# HotelRail.net
KiCad netlist of a schematic drawn in Altium Designer
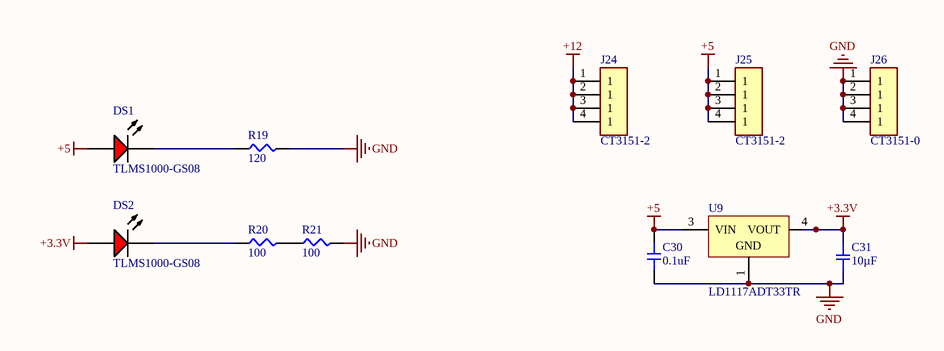
[diagram p0: HotelRail.SchDoc]

(export (version "E")
  (design (tool "Eeschema 10.0.6"))
  (components
    (comp (ref "C30")
      (value "0.1uF")
      (description "0.1uF, 0603, +/- 10%, 50V, X7R")
      (fields (field (name "TOLERANCE") "+/- 10%") (field (name "MFG") "TDK Corporation"))
      (libsource (lib "PV Buck v2 Lib") (part "C1608X7R1H104K080AA"))
    )
    (comp (ref "C31")
      (value "10µF")
      (footprint "PV Buck v2 Lib:SMD-0603-RES")
      (description "CAP CER 10UF 6.3V X5R 0603")
      (fields
        (field (name "PART NUMBER") "GRM188R60J106ME47D")
        (field (name "DIGI-KEY PART NUMBER") "490-3896-1-ND")
      )
      (libsource (lib "PV Buck v2 Lib") (part "GRM188R60J106ME47D"))
    )
    (comp (ref "DS1")
      (value "TLMS1000-GS08")
      (footprint "VISH-TLMS1000_V")
      (description "Low Current LED, 40 mW, 1.8 V, -40 to 100 degC, 2-Pin SMD (0603), RoHS, Tape and Reel")
      (fields (field (name "MANUFACTURER") "Vishay"))
      (libsource (lib "PV Buck v2 Lib") (part "CMP-2000-07254-1"))
    )
    (comp (ref "DS2")
      (value "TLMS1000-GS08")
      (footprint "VISH-TLMS1000_V")
      (description "Low Current LED, 40 mW, 1.8 V, -40 to 100 degC, 2-Pin SMD (0603), RoHS, Tape and Reel")
      (fields (field (name "MANUFACTURER") "Vishay"))
      (libsource (lib "PV Buck v2 Lib") (part "CMP-2000-07254-1"))
    )
    (comp (ref "J24")
      (value "CT3151-2")
      (footprint "CALTEST_CT3151-2")
      (description "Banana Jack Connector Standard Banana Solder Red")
      (fields (field (name "MF") "{'manufacturer': u'Cal Test'}"))
      (libsource (lib "PV Buck v2 Lib") (part "CT3151-2_1"))
    )
    (comp (ref "J25")
      (value "CT3151-2")
      (footprint "CALTEST_CT3151-2")
      (description "Banana Jack Connector Standard Banana Solder Red")
      (fields (field (name "MF") "{'manufacturer': u'Cal Test'}"))
      (libsource (lib "PV Buck v2 Lib") (part "CT3151-2_1"))
    )
    (comp (ref "J26")
      (value "CT3151-0")
      (footprint "CT3151-0")
      (description "Banana Jack Connector Standard Banana Solder Red")
      (fields (field (name "MF") "{'manufacturer': u'Cal Test'}") (field (name "MP") "CT3151-2"))
      (libsource (lib "PV Buck v2 Lib") (part "CT3151-2"))
    )
    (comp (ref "R19")
      (value "120")
      (footprint "SMD-0603-RES")
      (description "RES SMD 120 OHM 1% 1/10W 0603")
      (fields (field (name "PART NUMBER") "ERJ-3EKF1200V") (field (name "DIGI-KEY PART NUMBER") "P120HCT-ND"))
      (libsource (lib "PV Buck v2 Lib") (part "ERJ-3EKF1200V"))
    )
    (comp (ref "R20")
      (value "100")
      (footprint "SMD-0603-RES")
      (description "RES SMD 100 OHM 1% 1/10W 0603")
      (fields (field (name "PART NUMBER") "ERJ-3EKF1000V") (field (name "DIGI-KEY PART NUMBER") "P100HCT-ND"))
      (libsource (lib "PV Buck v2 Lib") (part "ERJ-3EKF1000V"))
    )
    (comp (ref "R21")
      (value "100")
      (footprint "SMD-0603-RES")
      (description "RES SMD 100 OHM 1% 1/10W 0603")
      (fields (field (name "PART NUMBER") "ERJ-3EKF1000V") (field (name "DIGI-KEY PART NUMBER") "P100HCT-ND"))
      (libsource (lib "PV Buck v2 Lib") (part "ERJ-3EKF1000V"))
    )
    (comp (ref "U9")
      (value "LD1117ADT33TR")
      (footprint "TO-252_L")
      (description "1A, Low Drop Positive Voltage Regulator, 3.3V, 3-Pin DPAK, Tape and Reel")
      (fields (field (name "MANUFACTURER") "STMicroelectronics"))
      (libsource (lib "PV Buck v2 Lib") (part "CMP-0244-00137-1"))
    )
  )
  (nets
    (net (code "1") (name "+3.3V") (class "Default")
      (node (ref "C31") (pin "1") (pinfunction "1_1") (pintype "passive"))
      (node (ref "DS2") (pin "1") (pinfunction "A_1") (pintype "passive"))
      (node (ref "U9") (pin "4") (pinfunction "VOUT_4") (pintype "power_in"))
    )
    (net (code "2") (name "+5") (class "Default")
      (node (ref "C30") (pin "2") (pinfunction "2_2") (pintype "passive"))
      (node (ref "DS1") (pin "1") (pinfunction "A_1") (pintype "passive"))
      (node (ref "J25") (pin "1") (pinfunction "1_1") (pintype "passive"))
      (node (ref "J25") (pin "2") (pinfunction "1_2") (pintype "passive"))
      (node (ref "J25") (pin "3") (pinfunction "1_3") (pintype "passive"))
      (node (ref "J25") (pin "4") (pinfunction "1_4") (pintype "passive"))
      (node (ref "U9") (pin "3") (pinfunction "VIN_3") (pintype "power_in"))
    )
    (net (code "3") (name "+12") (class "Default")
      (node (ref "J24") (pin "1") (pinfunction "1_1") (pintype "passive"))
      (node (ref "J24") (pin "2") (pinfunction "1_2") (pintype "passive"))
      (node (ref "J24") (pin "3") (pinfunction "1_3") (pintype "passive"))
      (node (ref "J24") (pin "4") (pinfunction "1_4") (pintype "passive"))
    )
    (net (code "4") (name "GND") (class "Default")
      (node (ref "C30") (pin "1") (pinfunction "1_1") (pintype "passive"))
      (node (ref "C31") (pin "2") (pinfunction "2_2") (pintype "passive"))
      (node (ref "J26") (pin "1") (pinfunction "1_1") (pintype "passive"))
      (node (ref "J26") (pin "2") (pinfunction "1_2") (pintype "passive"))
      (node (ref "J26") (pin "3") (pinfunction "1_3") (pintype "passive"))
      (node (ref "J26") (pin "4") (pinfunction "1_4") (pintype "passive"))
      (node (ref "R19") (pin "2") (pinfunction "2_2") (pintype "passive"))
      (node (ref "R21") (pin "2") (pinfunction "2_2") (pintype "passive"))
      (node (ref "U9") (pin "1") (pinfunction "GND_1") (pintype "power_in"))
    )
    (net (code "5") (name "Net-(DS1-K)") (class "Default")
      (node (ref "DS1") (pin "2") (pinfunction "K_2") (pintype "passive"))
      (node (ref "R19") (pin "1") (pinfunction "1_1") (pintype "passive"))
    )
    (net (code "6") (name "Net-(DS2-K)") (class "Default")
      (node (ref "DS2") (pin "2") (pinfunction "K_2") (pintype "passive"))
      (node (ref "R20") (pin "1") (pinfunction "1_1") (pintype "passive"))
    )
    (net (code "7") (name "Net-(R20-Pad2)") (class "Default")
      (node (ref "R20") (pin "2") (pinfunction "2_2") (pintype "passive"))
      (node (ref "R21") (pin "1") (pinfunction "1_1") (pintype "passive"))
    )
  )
)
